# AudioMonitor_Schem.net
KiCad netlist of a schematic drawn in Altium Designer
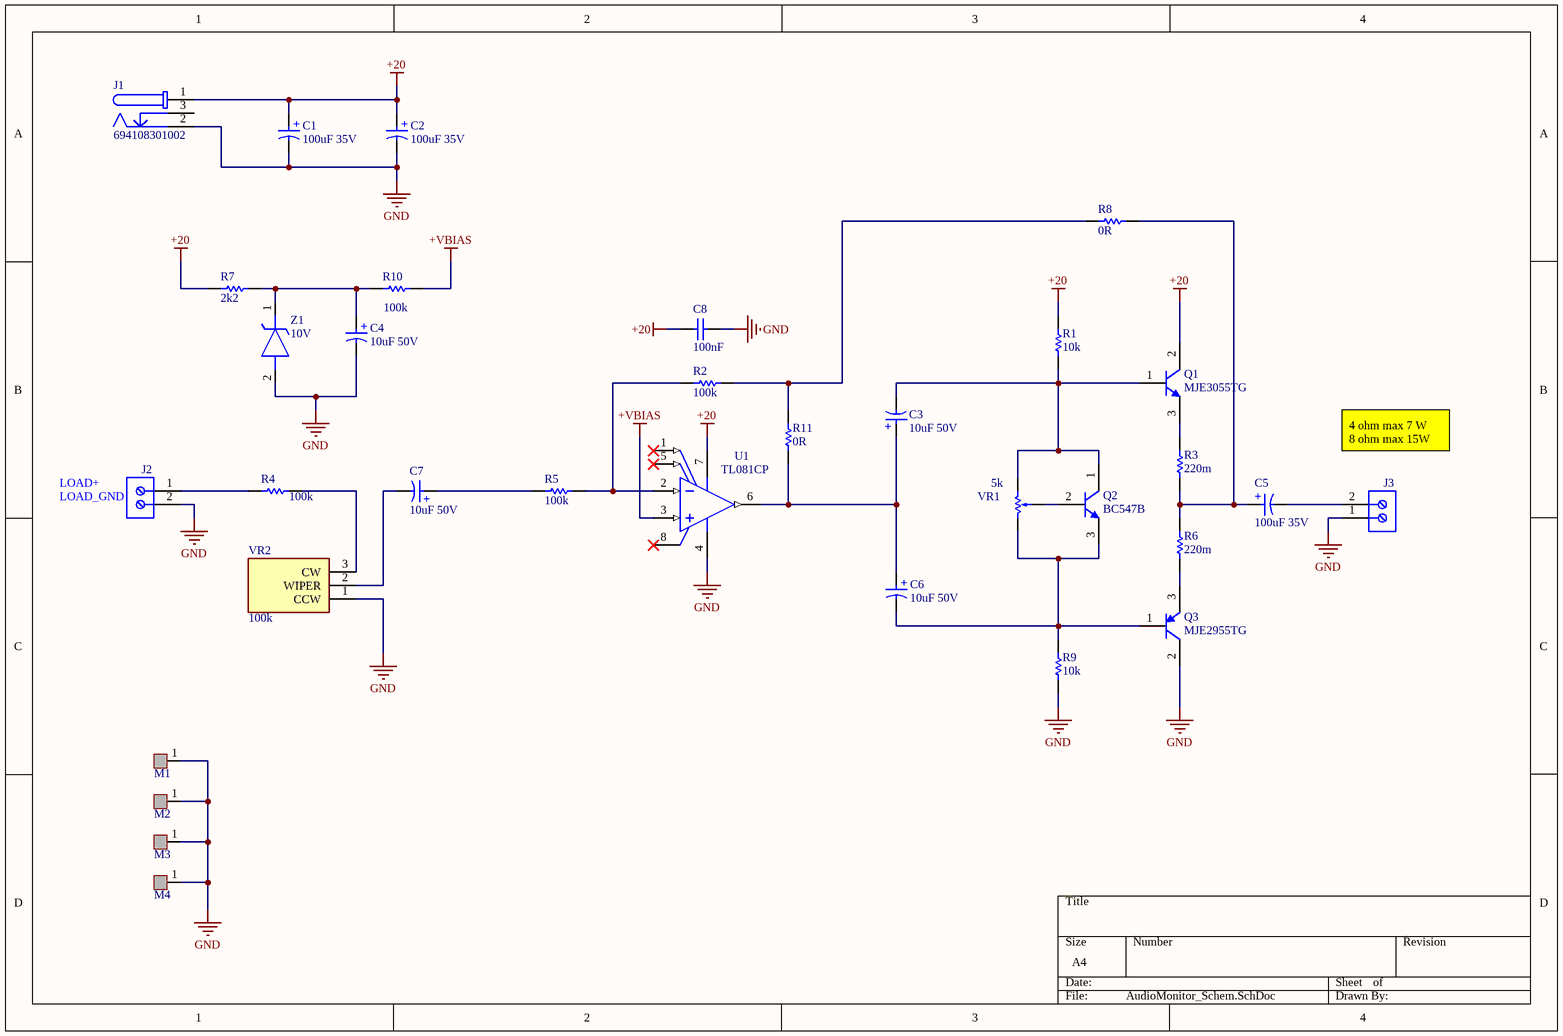
[diagram p0: AudioMonitor_Schem.SchDoc]

(export (version "E")
  (design (tool "Eeschema 10.0.6"))
  (components
    (comp (ref "C1")
      (value "100uF 35V")
      (footprint "Wurth D6.3x7.7mm")
      (description "SMD,D6.3xL7.7mm")
      (fields (field (name "Comment") "ROQANG RVT1V101M0607"))
      (libsource (lib "Electrolytic_Capacitors") (part "100uF 35V SMD"))
    )
    (comp (ref "C2")
      (value "100uF 35V")
      (footprint "Wurth D6.3x7.7mm")
      (description "SMD,D6.3xL7.7mm")
      (fields (field (name "Comment") "ROQANG RVT1V101M0607"))
      (libsource (lib "Electrolytic_Capacitors") (part "100uF 35V SMD"))
    )
    (comp (ref "C3")
      (value "AISHI CE-10/50PHT-Y")
      (footprint "WURTH THT CAP D5H11 P2mm")
      (description "Aluminum Electrolytic Capacitor, Radial, THT, D5 x H11mm, 10uF, 50V")
      (fields
        (field (name "MANUFACTURER PART NUMBER") "860010672009")
        (field (name "MANUFACTURER") "Wurth Elektronik")
        (field (name "CAPACITANCE") "10uF 50V")
      )
      (libsource (lib "Electrolytic_Capacitors") (part "10uF 50V THT"))
    )
    (comp (ref "C4")
      (value "AISHI CE-10/50PHT-Y")
      (footprint "WURTH THT CAP D5H11 P2mm")
      (description "Aluminum Electrolytic Capacitor, Radial, THT, D5 x H11mm, 10uF, 50V")
      (fields
        (field (name "MANUFACTURER PART NUMBER") "860010672009")
        (field (name "MANUFACTURER") "Wurth Elektronik")
        (field (name "CAPACITANCE") "10uF 50V")
      )
      (libsource (lib "Electrolytic_Capacitors") (part "10uF 50V THT"))
    )
    (comp (ref "C5")
      (value "100uF 35V")
      (footprint "Wurth D6.3x7.7mm")
      (description "SMD,D6.3xL7.7mm")
      (fields (field (name "Comment") "ROQANG RVT1V101M0607"))
      (libsource (lib "Electrolytic_Capacitors") (part "100uF 35V SMD"))
    )
    (comp (ref "C6")
      (value "AISHI CE-10/50PHT-Y")
      (footprint "WURTH THT CAP D5H11 P2mm")
      (description "Aluminum Electrolytic Capacitor, Radial, THT, D5 x H11mm, 10uF, 50V")
      (fields
        (field (name "MANUFACTURER PART NUMBER") "860010672009")
        (field (name "MANUFACTURER") "Wurth Elektronik")
        (field (name "CAPACITANCE") "10uF 50V")
      )
      (libsource (lib "Electrolytic_Capacitors") (part "10uF 50V THT"))
    )
    (comp (ref "C7")
      (value "AISHI CE-10/50PHT-Y")
      (footprint "WURTH THT CAP D5H11 P2mm")
      (description "Aluminum Electrolytic Capacitor, Radial, THT, D5 x H11mm, 10uF, 50V")
      (fields
        (field (name "MANUFACTURER PART NUMBER") "860010672009")
        (field (name "MANUFACTURER") "Wurth Elektronik")
        (field (name "CAPACITANCE") "10uF 50V")
      )
      (libsource (lib "Electrolytic_Capacitors") (part "10uF 50V THT"))
    )
    (comp (ref "C8")
      (value "100nF")
      (footprint "Wurth 0603 capacitor")
      (fields (field (name "Comment") "Capacitor 100nF 0603 50V"))
      (libsource (lib "Passives") (part "Capacitor 100nF 0603 50V"))
    )
    (comp (ref "J1")
      (value "694108301002")
      (footprint "694108301002")
      (description "DC Power Jack Connector WR-DC, Male, Right Angled, THT, 5 A, 24 V")
      (libsource (lib "Altium Content Vault") (part "DC Power Jack"))
    )
    (comp (ref "J2")
      (value "691101710002")
      (footprint "Wurth 2 pin 5mm screw terminal")
      (description "WR-TBL Series 101 Horizontal Entry Modular, THT, pitch 5mm, 02p")
      (fields (field (name "MANUFACTURER") "Wurth Elektronik"))
      (libsource (lib "Connectors") (part "2 pin 5mm screw terminal"))
    )
    (comp (ref "J3")
      (value "691101710002")
      (footprint "Wurth 2 pin 5mm screw terminal")
      (description "WR-TBL Series 101 Horizontal Entry Modular, THT, pitch 5mm, 02p")
      (fields (field (name "MANUFACTURER") "Wurth Elektronik"))
      (libsource (lib "Connectors") (part "2 pin 5mm screw terminal"))
    )
    (comp (ref "M1")
      (value "Mounting hole")
      (footprint "M3 hole")
      (libsource (lib "Mechanical") (part "Mounting hole"))
    )
    (comp (ref "M2")
      (value "Mounting hole")
      (footprint "M3 hole")
      (libsource (lib "Mechanical") (part "Mounting hole"))
    )
    (comp (ref "M3")
      (value "Mounting hole")
      (footprint "M3 hole")
      (libsource (lib "Mechanical") (part "Mounting hole"))
    )
    (comp (ref "M4")
      (value "Mounting hole")
      (footprint "M3 hole")
      (libsource (lib "Mechanical") (part "Mounting hole"))
    )
    (comp (ref "Q1")
      (value "MJE3055TG")
      (footprint "ONSC-TO-220-3-221A-09")
      (description "Complementary Silicon Plastic Power Transistor, 3-Pin TO-220, Pb-Free, Tube")
      (fields (field (name "MANUFACTURER") "On Semiconductor"))
      (libsource (lib "Altium Content Vault") (part "ONSC-NPN-B1C2E3-3_C"))
    )
    (comp (ref "Q2")
      (value "BC547B")
      (footprint "ONSC-TO-92-3-29-11")
      (description "Amplifier Transistor, NPN Silicon, 3-Pin TO-92, Bulk Box")
      (fields (field (name "MANUFACTURER") "On Semiconductor"))
      (libsource (lib "Altium Content Vault") (part "ONSC-NPN-C1B2E3-3"))
    )
    (comp (ref "Q3")
      (value "MJE2955TG")
      (footprint "ONSC-TO-220-3-221A-09")
      (description "Complementary Silicon Plastic Power Transistor, 3-Pin TO-220, Pb-Free, Tube")
      (fields (field (name "MANUFACTURER") "On Semiconductor"))
      (libsource (lib "Altium Content Vault") (part "ONSC-PNP-B1C2E3-3"))
    )
    (comp (ref "R1")
      (value "10k")
      (footprint "Wurth 0603 Resistor")
      (fields (field (name "Comment") "Resistor 10k 0603"))
      (libsource (lib "Passives") (part "Resistor 10k 0603"))
    )
    (comp (ref "R2")
      (value "100k")
      (footprint "Wurth 0603 Resistor")
      (fields (field (name "Comment") "Resistor 100k 0603"))
      (libsource (lib "Passives") (part "Resistor 100k 0603"))
    )
    (comp (ref "R3")
      (value "220m")
      (footprint "Viking 2010 Resistor")
      (fields (field (name "Comment") "Resistor 220m 2010"))
      (libsource (lib "Passives") (part "Resistor 220m 2010"))
    )
    (comp (ref "R4")
      (value "100k")
      (footprint "Wurth 0603 Resistor")
      (fields (field (name "Comment") "Resistor 100k 0603"))
      (libsource (lib "Passives") (part "Resistor 100k 0603"))
    )
    (comp (ref "R5")
      (value "100k")
      (footprint "Wurth 0603 Resistor")
      (fields (field (name "Comment") "Resistor 100k 0603"))
      (libsource (lib "Passives") (part "Resistor 100k 0603"))
    )
    (comp (ref "R6")
      (value "220m")
      (footprint "Viking 2010 Resistor")
      (fields (field (name "Comment") "Resistor 220m 2010"))
      (libsource (lib "Passives") (part "Resistor 220m 2010"))
    )
    (comp (ref "R7")
      (value "2k2")
      (footprint "Wurth 0603 Resistor")
      (fields (field (name "Comment") "Resistor 2k2 0603"))
      (libsource (lib "Passives") (part "Resistor 2k2 0603"))
    )
    (comp (ref "R8")
      (value "0R")
      (footprint "Wurth 0603 Resistor")
      (fields (field (name "Comment") "Resistor 0R 0603"))
      (libsource (lib "Passives") (part "Resistor 0R 0603"))
    )
    (comp (ref "R9")
      (value "10k")
      (footprint "Wurth 0603 Resistor")
      (fields (field (name "Comment") "Resistor 10k 0603"))
      (libsource (lib "Passives") (part "Resistor 10k 0603"))
    )
    (comp (ref "R10")
      (value "100k")
      (footprint "Wurth 0603 Resistor")
      (fields (field (name "Comment") "Resistor 100k 0603"))
      (libsource (lib "Passives") (part "Resistor 100k 0603"))
    )
    (comp (ref "R11")
      (value "0R")
      (footprint "Wurth 0603 Resistor")
      (fields (field (name "Comment") "Resistor 0R 0603"))
      (libsource (lib "Passives") (part "Resistor 0R 0603"))
    )
    (comp (ref "U1")
      (value "TL081CP")
      (footprint "P0008A")
      (description "JFET-Input Operational Amplifier, 7 to 36 V, 0 to 70 degC, 8-pin DIP (P8), Pb-Free (RoHS)")
      (fields (field (name "MANUFACTURER") "Texas Instruments"))
      (libsource (lib "Altium Content Vault") (part "TI-AMP-S5-2-8"))
    )
    (comp (ref "VR1")
      (value "5k")
      (footprint "SRpassives RKT6V-5K")
      (fields (field (name "Comment") "RKT6V-5K"))
      (libsource (lib "Potentiometer") (part "5k THT trimmer"))
    )
    (comp (ref "VR2")
      (value "100k")
      (footprint "SamacSys:PDB181K215P503B")
      (description "Variable Resistor")
      (fields
        (field (name "MANUFACTURER_PART_NUMBER") "PDB181-K215P-503B")
        (field (name "MOUSER PART NUMBER") "652-PDB181K215P503B")
      )
      (libsource (lib "*") (part "PDB181-K215P-503B"))
    )
    (comp (ref "Z1")
      (value "10V")
      (footprint "SamacSys:BZT52C10TTP")
      (description "Zener Diode")
      (fields
        (field (name "MANUFACTURER_PART_NUMBER") "BZT52C10T-TP")
        (field (name "MOUSER PART NUMBER") "833-BZT52C10T-TP")
      )
      (libsource (lib "*") (part "BZT52C10T-TP"))
    )
  )
  (nets
    (net (code "1") (name "+20") (class "Default")
      (node (ref "C1") (pin "1") (pinfunction "P_1") (pintype "passive"))
      (node (ref "C2") (pin "1") (pinfunction "P_1") (pintype "passive"))
      (node (ref "C8") (pin "1") (pinfunction "1_1") (pintype "passive"))
      (node (ref "J1") (pin "1") (pinfunction "1_1") (pintype "passive"))
      (node (ref "Q1") (pin "2") (pinfunction "C_2") (pintype "passive"))
      (node (ref "R1") (pin "2") (pinfunction "2_2") (pintype "passive"))
      (node (ref "R7") (pin "2") (pinfunction "2_2") (pintype "passive"))
      (node (ref "U1") (pin "7") (pinfunction "VCC+_7") (pintype "power_in"))
    )
    (net (code "2") (name "+VBIAS") (class "Default")
      (node (ref "R10") (pin "1") (pinfunction "1_1") (pintype "passive"))
      (node (ref "U1") (pin "3") (pinfunction "IN+_3") (pintype "input"))
    )
    (net (code "3") (name "GND") (class "Default")
      (node (ref "C1") (pin "2") (pinfunction "N_2") (pintype "passive"))
      (node (ref "C2") (pin "2") (pinfunction "N_2") (pintype "passive"))
      (node (ref "C4") (pin "2") (pinfunction "N_2") (pintype "passive"))
      (node (ref "C8") (pin "2") (pinfunction "2_2") (pintype "passive"))
      (node (ref "J1") (pin "2") (pinfunction "2_2") (pintype "passive"))
      (node (ref "J2") (pin "2") (pinfunction "2_2") (pintype "passive"))
      (node (ref "J3") (pin "1") (pinfunction "1_1") (pintype "passive"))
      (node (ref "M1") (pin "1") (pinfunction "1_1") (pintype "passive"))
      (node (ref "M2") (pin "1") (pinfunction "1_1") (pintype "passive"))
      (node (ref "M3") (pin "1") (pinfunction "1_1") (pintype "passive"))
      (node (ref "M4") (pin "1") (pinfunction "1_1") (pintype "passive"))
      (node (ref "Q3") (pin "2") (pinfunction "C_2") (pintype "passive"))
      (node (ref "R9") (pin "1") (pinfunction "1_1") (pintype "passive"))
      (node (ref "U1") (pin "4") (pinfunction "VCC-_4") (pintype "power_in"))
      (node (ref "VR2") (pin "1") (pinfunction "CCW_1") (pintype "passive"))
      (node (ref "Z1") (pin "2") (pinfunction "A_2") (pintype "passive"))
    )
    (net (code "4") (name "Net-(C3-N)") (class "Default")
      (node (ref "C3") (pin "2") (pinfunction "N_2") (pintype "passive"))
      (node (ref "Q1") (pin "1") (pinfunction "B_1") (pintype "passive"))
      (node (ref "Q2") (pin "1") (pinfunction "C_1") (pintype "passive"))
      (node (ref "R1") (pin "1") (pinfunction "1_1") (pintype "passive"))
      (node (ref "VR1") (pin "3") (pinfunction "3_3") (pintype "passive"))
    )
    (net (code "5") (name "Net-(C3-P)") (class "Default")
      (node (ref "C3") (pin "1") (pinfunction "P_1") (pintype "passive"))
      (node (ref "C6") (pin "1") (pinfunction "P_1") (pintype "passive"))
      (node (ref "R11") (pin "1") (pinfunction "1_1") (pintype "passive"))
      (node (ref "U1") (pin "6") (pinfunction "OUT_6") (pintype "output"))
    )
    (net (code "6") (name "Net-(C4-P)") (class "Default")
      (node (ref "C4") (pin "1") (pinfunction "P_1") (pintype "passive"))
      (node (ref "R10") (pin "2") (pinfunction "2_2") (pintype "passive"))
      (node (ref "R7") (pin "1") (pinfunction "1_1") (pintype "passive"))
      (node (ref "Z1") (pin "1") (pinfunction "K_1") (pintype "passive"))
    )
    (net (code "7") (name "Net-(C5-N)") (class "Default")
      (node (ref "C5") (pin "2") (pinfunction "N_2") (pintype "passive"))
      (node (ref "J3") (pin "2") (pinfunction "2_2") (pintype "passive"))
    )
    (net (code "8") (name "Net-(C5-P)") (class "Default")
      (node (ref "C5") (pin "1") (pinfunction "P_1") (pintype "passive"))
      (node (ref "R3") (pin "1") (pinfunction "1_1") (pintype "passive"))
      (node (ref "R6") (pin "2") (pinfunction "2_2") (pintype "passive"))
      (node (ref "R8") (pin "2") (pinfunction "2_2") (pintype "passive"))
    )
    (net (code "9") (name "Net-(C6-N)") (class "Default")
      (node (ref "C6") (pin "2") (pinfunction "N_2") (pintype "passive"))
      (node (ref "Q2") (pin "3") (pinfunction "E_3") (pintype "passive"))
      (node (ref "Q3") (pin "1") (pinfunction "B_1") (pintype "passive"))
      (node (ref "R9") (pin "2") (pinfunction "2_2") (pintype "passive"))
      (node (ref "VR1") (pin "1") (pinfunction "1_1") (pintype "passive"))
    )
    (net (code "10") (name "Net-(C7-N)") (class "Default")
      (node (ref "C7") (pin "2") (pinfunction "N_2") (pintype "passive"))
      (node (ref "VR2") (pin "2") (pinfunction "WIPER_2") (pintype "passive"))
    )
    (net (code "11") (name "Net-(C7-P)") (class "Default")
      (node (ref "C7") (pin "1") (pinfunction "P_1") (pintype "passive"))
      (node (ref "R5") (pin "1") (pinfunction "1_1") (pintype "passive"))
    )
    (net (code "12") (name "Net-(J2-Pad1)") (class "Default")
      (node (ref "J2") (pin "1") (pinfunction "1_1") (pintype "passive"))
      (node (ref "R4") (pin "1") (pinfunction "1_1") (pintype "passive"))
    )
    (net (code "13") (name "Net-(Q1-E)") (class "Default")
      (node (ref "Q1") (pin "3") (pinfunction "E_3") (pintype "passive"))
      (node (ref "R3") (pin "2") (pinfunction "2_2") (pintype "passive"))
    )
    (net (code "14") (name "Net-(Q2-B)") (class "Default")
      (node (ref "Q2") (pin "2") (pinfunction "B_2") (pintype "passive"))
      (node (ref "VR1") (pin "2") (pinfunction "2_2") (pintype "passive"))
    )
    (net (code "15") (name "Net-(Q3-E)") (class "Default")
      (node (ref "Q3") (pin "3") (pinfunction "E_3") (pintype "passive"))
      (node (ref "R6") (pin "1") (pinfunction "1_1") (pintype "passive"))
    )
    (net (code "16") (name "Net-(R11-Pad2)") (class "Default")
      (node (ref "R11") (pin "2") (pinfunction "2_2") (pintype "passive"))
      (node (ref "R2") (pin "2") (pinfunction "2_2") (pintype "passive"))
      (node (ref "R8") (pin "1") (pinfunction "1_1") (pintype "passive"))
    )
    (net (code "17") (name "Net-(U1-IN-)") (class "Default")
      (node (ref "R2") (pin "1") (pinfunction "1_1") (pintype "passive"))
      (node (ref "R5") (pin "2") (pinfunction "2_2") (pintype "passive"))
      (node (ref "U1") (pin "2") (pinfunction "IN-_2") (pintype "input"))
    )
    (net (code "18") (name "Net-(VR2-CW)") (class "Default")
      (node (ref "R4") (pin "2") (pinfunction "2_2") (pintype "passive"))
      (node (ref "VR2") (pin "3") (pinfunction "CW_3") (pintype "passive"))
    )
    (net (code "19") (name "unconnected-(J1-Pad3)") (class "Default")
      (node (ref "J1") (pin "3") (pinfunction "3_3") (pintype "passive"))
    )
    (net (code "20") (name "unconnected-(U1-NC-Pad8)") (class "Default")
      (node (ref "U1") (pin "8") (pinfunction "NC_8") (pintype "passive+no_connect"))
    )
    (net (code "21") (name "unconnected-(U1-OFFSET_N1-Pad1)") (class "Default")
      (node (ref "U1") (pin "1") (pinfunction "OFFSET_N1_1") (pintype "input+no_connect"))
    )
    (net (code "22") (name "unconnected-(U1-OFFSET_N2-Pad5)") (class "Default")
      (node (ref "U1") (pin "5") (pinfunction "OFFSET_N2_5") (pintype "input+no_connect"))
    )
  )
)
